# Connectors.net
KiCad netlist of a schematic drawn in Altium Designer
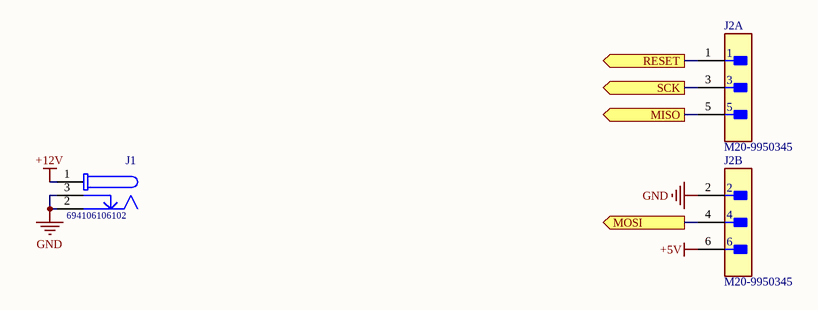
[diagram p0: Connectors.SchDoc]

(export (version "E")
  (design (tool "Eeschema 10.0.6"))
  (components
    (comp (ref "J1")
      (value "694106106102")
      (footprint "694106106102")
      (description "DC Power Jack Connector with 4 soldering pads & Pegs WR-DC, Male, Right Angled, SMT, 5 A, 24 V")
      (fields (field (name "MANUFACTURER") "Wurth Elektronik") (field (name "PUBLISHER") "WurthElektronik"))
      (libsource (lib "Altium Content Vault") (part "WE-JACK-2CD3-RN"))
    )
    (comp (ref "J2")
      (value "M20-9950345")
      (footprint "FP-M20-9950345-MFG")
      (description "CONN HEADER R/A 6POS 2.54MM")
      (fields
        (field (name "OCTOPART") "https://octopart.com/m20-9950345-harwin-21265213")
        (field (name "MANUFACTURER") "Harwin")
      )
      (libsource (lib "Altium Content Vault") (part "b76336891f9c52daa0497ceff74f613"))
    )
  )
  (nets
    (net (code "1") (name "+5V") (class "Default")
      (node (ref "J2") (pin "6") (pinfunction "6_6") (pintype "passive"))
    )
    (net (code "2") (name "+12V") (class "Default")
      (node (ref "J1") (pin "1") (pinfunction "1_1") (pintype "passive"))
    )
    (net (code "3") (name "/MISO") (class "Default")
      (node (ref "J2") (pin "5") (pinfunction "5_5") (pintype "passive"))
    )
    (net (code "4") (name "/MOSI") (class "Default")
      (node (ref "J2") (pin "4") (pinfunction "4_4") (pintype "passive"))
    )
    (net (code "5") (name "/RESET") (class "Default")
      (node (ref "J2") (pin "1") (pinfunction "1_1") (pintype "passive"))
    )
    (net (code "6") (name "/SCK") (class "Default")
      (node (ref "J2") (pin "3") (pinfunction "3_3") (pintype "passive"))
    )
    (net (code "7") (name "GND") (class "Default")
      (node (ref "J1") (pin "2") (pinfunction "2_2") (pintype "passive"))
      (node (ref "J1") (pin "3") (pinfunction "3_3") (pintype "passive"))
      (node (ref "J2") (pin "2") (pinfunction "2_2") (pintype "passive"))
    )
  )
)
